# 3_3V_CAN_Tranceiver.net
KiCad netlist of a schematic drawn in Altium Designer
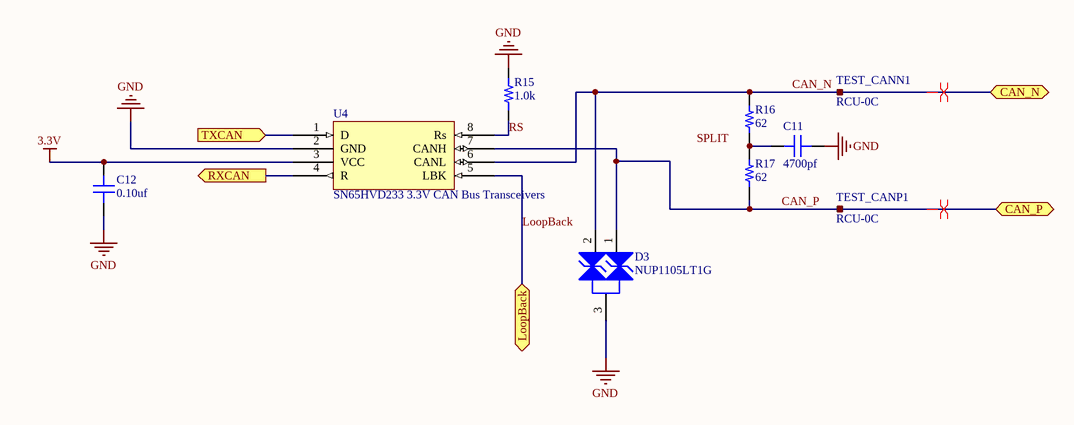
[diagram p0: 3.3V CAN_Tranceiver.SchDoc]

(export (version "E")
  (design (tool "Eeschema 10.0.6"))
  (components
    (comp (ref "C11")
      (value "4700pf")
      (footprint "CAP 0603/1608")
      (fields
        (field (name "Comment") "Capacitor MLCC 4700pf 50V CAP 0603/1608")
        (field (name "CREATED_BY") "Nick Mah")
      )
      (libsource (lib "Altium-Lib") (part "Capacitor"))
    )
    (comp (ref "C12")
      (value "0.10uf")
      (footprint "CAP 0603/1608")
      (fields
        (field (name "Comment") "Capacitor MLCC 0.10uf 50V CAP 0603/1608")
        (field (name "CREATED_BY") "Nick Mah")
      )
      (libsource (lib "Altium-Lib") (part "Capacitor"))
    )
    (comp (ref "D3")
      (value "NUP1105LT1G")
      (footprint "SOT-23 (TO-236)")
      (description "ESD Protection Diode")
      (fields (field (name "POWER") "350W"))
      (libsource (lib "Altium-Lib") (part "NUP1105LT1G"))
    )
    (comp (ref "R15")
      (value "1.0k")
      (footprint "RES 0603/1608")
      (fields
        (field (name "TOLERANCE") "1%")
        (field (name "POWER") "1/10W")
        (field (name "Comment") "Resistor 1.0k 0603 1/10W 1%")
        (field (name "CREATED_BY") "Nick Mah")
      )
      (libsource (lib "") (part "Resistor_1"))
    )
    (comp (ref "R16")
      (value "62")
      (footprint "RES 0603/1608")
      (fields
        (field (name "TOLERANCE") "5%")
        (field (name "POWER") "1/10W")
        (field (name "Comment") "Resistor 62 0603 1/10W 5%")
        (field (name "CREATED_BY") "Nick Mah")
      )
      (libsource (lib "Altium-Lib") (part "Resistor"))
    )
    (comp (ref "R17")
      (value "62")
      (footprint "RES 0603/1608")
      (fields
        (field (name "TOLERANCE") "5%")
        (field (name "POWER") "1/10W")
        (field (name "Comment") "Resistor 62 0603 1/10W 5%")
        (field (name "CREATED_BY") "Nick Mah")
      )
      (libsource (lib "Altium-Lib") (part "Resistor"))
    )
    (comp (ref "TEST_CANN1")
      (value "RCU-0C")
      (footprint "RCU-0C")
      (libsource (lib "Altium-Lib") (part "RCU-0C"))
    )
    (comp (ref "TEST_CANP1")
      (value "RCU-0C")
      (footprint "RCU-0C")
      (libsource (lib "Altium-Lib") (part "RCU-0C"))
    )
    (comp (ref "U4")
      (value "SN65HVD233 3.3V CAN Bus Transceivers")
      (footprint "SOIC-8")
      (description "1/1 Transceiver Half CANbus 8-SOIC")
      (fields (field (name "MFRPARTNO") "SN65HVD233D"))
      (libsource (lib "Altium-Lib") (part "SN65HVD233 3.3V CAN Bus Transceivers"))
    )
  )
  (nets
    (net (code "1") (name "/CAN_N") (class "Default")
      (node (ref "D3") (pin "2") (pinfunction "K_2") (pintype "passive"))
      (node (ref "R16") (pin "1") (pinfunction "1_1") (pintype "passive"))
      (node (ref "TEST_CANN1") (pin "1") (pintype "passive"))
      (node (ref "U4") (pin "6") (pinfunction "CANL_6") (pintype "bidirectional"))
    )
    (net (code "2") (name "/CAN_P") (class "Default")
      (node (ref "D3") (pin "1") (pinfunction "K_1") (pintype "passive"))
      (node (ref "R17") (pin "2") (pinfunction "2_2") (pintype "passive"))
      (node (ref "TEST_CANP1") (pin "1") (pintype "passive"))
      (node (ref "U4") (pin "7") (pinfunction "CANH_7") (pintype "bidirectional"))
    )
    (net (code "3") (name "/LoopBack") (class "Default")
      (node (ref "U4") (pin "5") (pinfunction "LBK_5") (pintype "input"))
    )
    (net (code "4") (name "/RS") (class "Default")
      (node (ref "R15") (pin "1") (pinfunction "1_1") (pintype "passive"))
      (node (ref "U4") (pin "8") (pinfunction "Rs_8") (pintype "input"))
    )
    (net (code "5") (name "/RXCAN") (class "Default")
      (node (ref "U4") (pin "4") (pinfunction "R_4") (pintype "output"))
    )
    (net (code "7") (name "/TXCAN") (class "Default")
      (node (ref "U4") (pin "1") (pinfunction "D_1") (pintype "input"))
    )
    (net (code "8") (name "3.3V") (class "Default")
      (node (ref "C12") (pin "1") (pinfunction "1_1") (pintype "passive"))
      (node (ref "U4") (pin "3") (pinfunction "VCC_3") (pintype "power_in"))
    )
    (net (code "9") (name "GND") (class "Default")
      (node (ref "C11") (pin "1") (pinfunction "1_1") (pintype "passive"))
      (node (ref "C12") (pin "2") (pinfunction "2_2") (pintype "passive"))
      (node (ref "D3") (pin "3") (pinfunction "K_3") (pintype "passive"))
      (node (ref "R15") (pin "2") (pinfunction "2_2") (pintype "passive"))
      (node (ref "U4") (pin "2") (pinfunction "GND_2") (pintype "power_in"))
    )
    (net (code "10") (name "Net-(C11-Pad2)") (class "Default")
      (node (ref "C11") (pin "2") (pinfunction "2_2") (pintype "passive"))
      (node (ref "R16") (pin "2") (pinfunction "2_2") (pintype "passive"))
      (node (ref "R17") (pin "1") (pinfunction "1_1") (pintype "passive"))
    )
  )
)
